# LineFollower.net
KiCad netlist of a schematic drawn in Altium Designer
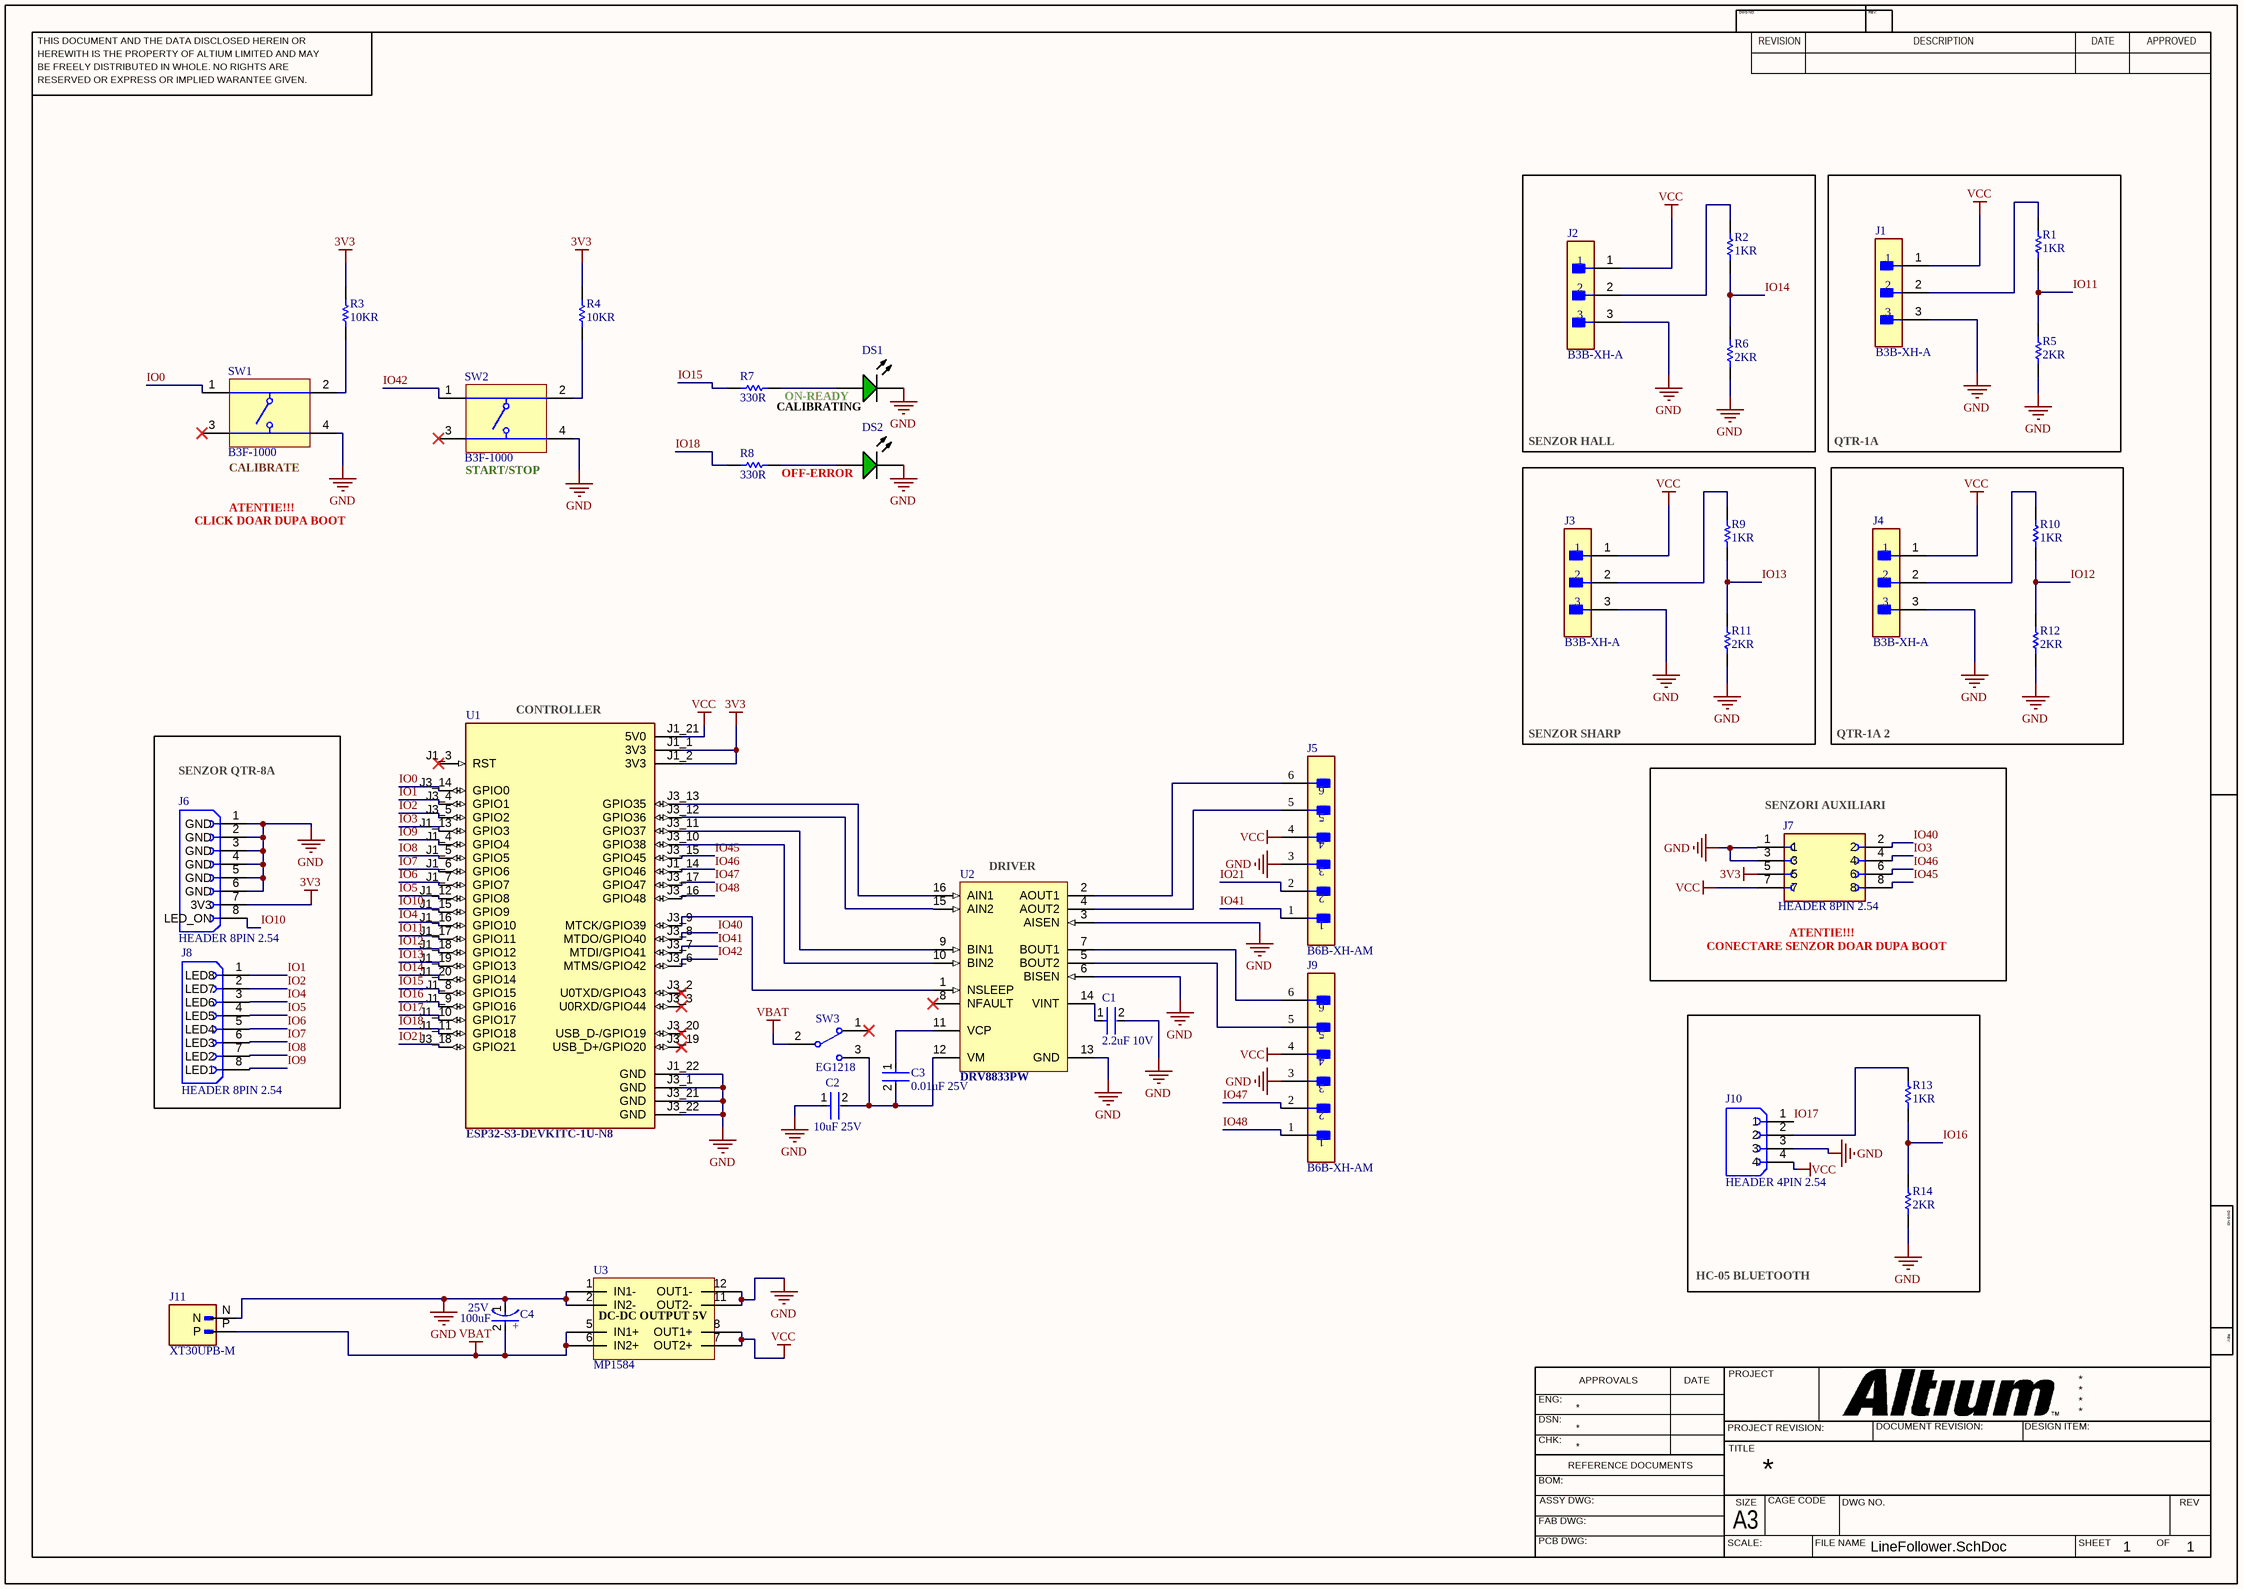
[diagram p0: LineFollower.SchDoc]

(export (version "E")
  (design (tool "Eeschema 10.0.6"))
  (components
    (comp (ref "C1")
      (value "2.2uF 10V")
      (footprint "FP-CL21-IPC_B")
      (description "CL21 Series 0805 10uF 25V ±20% Tolerance X5R Multilayer Ceramic Chip Capacitor")
      (libsource (lib "Altium Content Vault") (part "b4654b650e69147ec39a6b967a45e02"))
    )
    (comp (ref "C2")
      (value "10uF 25V")
      (footprint "FP-CL21-IPC_B")
      (description "CL21 Series 0805 10uF 25V ±20% Tolerance X5R Multilayer Ceramic Chip Capacitor")
      (libsource (lib "Altium Content Vault") (part "b4654b650e69147ec39a6b967a45e02"))
    )
    (comp (ref "C3")
      (value "0.01uF 25V")
      (footprint "FP-CL21-IPC_B")
      (description "CL21 Series 0805 10uF 25V ±20% Tolerance X5R Multilayer Ceramic Chip Capacitor")
      (libsource (lib "Altium Content Vault") (part "b4654b650e69147ec39a6b967a45e02"))
    )
    (comp (ref "C4")
      (value "EEUTA1E101")
      (footprint "FP-RAD-TH-D_8_0_5-L_11_5-MFG")
      (description "Aluminum Electrolytic Capacitors (Radial Lead Type) AEC-Q200 Qualified 100uF ±20% 25V")
      (fields
        (field (name "VOLTAGE") "25V")
        (field (name "TOLERANCE") "20%")
        (field (name "CAPACITANCE") "100uF")
      )
      (libsource (lib "Altium Content Vault") (part "203bc49f2ac43e59fd269a8c329ed05"))
    )
    (comp (ref "DS1")
      (value "304090040")
      (footprint "LED-2P-2.28-3MM")
      (description "Green LED, 80 mW, 20 mA, -25 to 85 degC, 2-Pin THD")
      (fields (field (name "MANUFACTURER") "Shenzhen CGX"))
      (libsource (lib "Costel Petrea3006") (part "LED-GREEN-AK-2"))
    )
    (comp (ref "DS2")
      (value "304090040")
      (footprint "LED-2P-2.28-3MM")
      (description "Green LED, 80 mW, 20 mA, -25 to 85 degC, 2-Pin THD")
      (fields (field (name "MANUFACTURER") "Shenzhen CGX"))
      (libsource (lib "Costel Petrea3006") (part "LED-GREEN-AK-2"))
    )
    (comp (ref "J1")
      (value "B3B-XH-A")
      (footprint "FP-B3B-XH-A_LF_SN-MFG")
      (description "CONN HEADER VERT 3POS 2.5MM")
      (libsource (lib "Altium Content Vault") (part "0d3f023dd272f625e17a2be33dea85f"))
    )
    (comp (ref "J2")
      (value "B3B-XH-A")
      (footprint "FP-B3B-XH-A_LF_SN-MFG")
      (description "CONN HEADER VERT 3POS 2.5MM")
      (libsource (lib "Altium Content Vault") (part "0d3f023dd272f625e17a2be33dea85f"))
    )
    (comp (ref "J3")
      (value "B3B-XH-A")
      (footprint "FP-B3B-XH-A_LF_SN-MFG")
      (description "CONN HEADER VERT 3POS 2.5MM")
      (libsource (lib "Altium Content Vault") (part "0d3f023dd272f625e17a2be33dea85f"))
    )
    (comp (ref "J4")
      (value "B3B-XH-A")
      (footprint "FP-B3B-XH-A_LF_SN-MFG")
      (description "CONN HEADER VERT 3POS 2.5MM")
      (libsource (lib "Altium Content Vault") (part "0d3f023dd272f625e17a2be33dea85f"))
    )
    (comp (ref "J5")
      (value "B6B-XH-AM")
      (footprint "FP-B6B-XH-AM_LF_SN-MFG")
      (description "CONN HEADER VERT 6POS 2.5MM")
      (libsource (lib "Altium Content Vault") (part "f2cb566baf1c37ab5a3b8e90bbeafd6"))
    )
    (comp (ref "J6")
      (value "HEADER 8PIN 2.54")
      (footprint "GRAVITECH_8FX1-254MM")
      (description "Headers & Wire Housings 2.54MM 0.1 8-PIN FEMALE HEADER")
      (fields (field (name "MP") "8Fx1-254mm") (field (name "MF") "Gravitech"))
      (libsource (lib "8FX1-254MM") (part "8FX1-254MM"))
    )
    (comp (ref "J7")
      (value "HEADER 8PIN 2.54")
      (footprint "SULLINS_PPPC042LFBN-RC")
      (description "8 Position Total Dual Row 2.54 mm Pitch Straight Female Header")
      (fields (field (name "MF") "Sullins Connector Solutions") (field (name "MP") "PPPC042LFBNRC"))
      (libsource (lib "PPPC042LFBN-RC") (part "PPPC042LFBN-RC"))
    )
    (comp (ref "J8")
      (value "HEADER 8PIN 2.54")
      (footprint "GRAVITECH_8FX1-254MM")
      (description "Headers & Wire Housings 2.54MM 0.1 8-PIN FEMALE HEADER")
      (fields (field (name "MP") "8Fx1-254mm") (field (name "MF") "Gravitech"))
      (libsource (lib "8FX1-254MM") (part "8FX1-254MM"))
    )
    (comp (ref "J9")
      (value "B6B-XH-AM")
      (footprint "FP-B6B-XH-AM_LF_SN-MFG")
      (description "CONN HEADER VERT 6POS 2.5MM")
      (libsource (lib "Altium Content Vault") (part "f2cb566baf1c37ab5a3b8e90bbeafd6"))
    )
    (comp (ref "J10")
      (value "HEADER 4PIN 2.54")
      (footprint "SULLINS_PPTC041LFBN-RC")
      (description "4 Position Header Connector 0.100 (2.54mm) Through Hole Tin")
      (fields (field (name "MF") "Sullins Connector") (field (name "MP") "PPTC041LFBN-RC"))
      (libsource (lib "PPTC041LFBN-RC") (part "PPTC041LFBN-RC"))
    )
    (comp (ref "J11")
      (value "XT30UPB-M")
      (footprint "AMASS_XT30UPB-M")
      (description "Socket; DC supply; XT30; male; PIN: 2; on PCBs; THT; yellow; 15A; 500V")
      (fields (field (name "MF") "amass"))
      (libsource (lib "XT30") (part "XT30UPB-M"))
    )
    (comp (ref "R1")
      (value "1KR")
      (footprint "RESC2013X60X30LL20T20")
      (fields (field (name "MANUFACTURER") "KOA Speer") (field (name "PART NUMBER") "SG73S2ATTD1002F"))
      (libsource (lib "Altium Content Vault") (part "RES"))
    )
    (comp (ref "R2")
      (value "1KR")
      (footprint "RESC2013X60X30LL20T20")
      (fields (field (name "MANUFACTURER") "KOA Speer") (field (name "PART NUMBER") "SG73S2ATTD1002F"))
      (libsource (lib "Altium Content Vault") (part "RES"))
    )
    (comp (ref "R3")
      (value "10KR")
      (footprint "RESC2013X60X30LL20T20")
      (fields (field (name "MANUFACTURER") "KOA Speer") (field (name "PART NUMBER") "SG73S2ATTD1002F"))
      (libsource (lib "Altium Content Vault") (part "RES"))
    )
    (comp (ref "R4")
      (value "10KR")
      (footprint "RESC2013X60X30LL20T20")
      (fields (field (name "MANUFACTURER") "KOA Speer") (field (name "PART NUMBER") "SG73S2ATTD1002F"))
      (libsource (lib "Altium Content Vault") (part "RES"))
    )
    (comp (ref "R5")
      (value "2KR")
      (footprint "RESC2013X60X30LL20T20")
      (fields (field (name "MANUFACTURER") "KOA Speer") (field (name "PART NUMBER") "SG73S2ATTD1002F"))
      (libsource (lib "Altium Content Vault") (part "RES"))
    )
    (comp (ref "R6")
      (value "2KR")
      (footprint "RESC2013X60X30LL20T20")
      (fields (field (name "MANUFACTURER") "KOA Speer") (field (name "PART NUMBER") "SG73S2ATTD1002F"))
      (libsource (lib "Altium Content Vault") (part "RES"))
    )
    (comp (ref "R7")
      (value "330R")
      (footprint "RESC2013X60X30LL20T20")
      (fields (field (name "MANUFACTURER") "KOA Speer") (field (name "PART NUMBER") "SG73S2ATTD1002F"))
      (libsource (lib "Altium Content Vault") (part "RES"))
    )
    (comp (ref "R8")
      (value "330R")
      (footprint "RESC2013X60X30LL20T20")
      (fields (field (name "MANUFACTURER") "KOA Speer") (field (name "PART NUMBER") "SG73S2ATTD1002F"))
      (libsource (lib "Altium Content Vault") (part "RES"))
    )
    (comp (ref "R9")
      (value "1KR")
      (footprint "RESC2013X60X30LL20T20")
      (fields (field (name "MANUFACTURER") "KOA Speer") (field (name "PART NUMBER") "SG73S2ATTD1002F"))
      (libsource (lib "Altium Content Vault") (part "RES"))
    )
    (comp (ref "R10")
      (value "1KR")
      (footprint "RESC2013X60X30LL20T20")
      (fields (field (name "MANUFACTURER") "KOA Speer") (field (name "PART NUMBER") "SG73S2ATTD1002F"))
      (libsource (lib "Altium Content Vault") (part "RES"))
    )
    (comp (ref "R11")
      (value "2KR")
      (footprint "RESC2013X60X30LL20T20")
      (fields (field (name "MANUFACTURER") "KOA Speer") (field (name "PART NUMBER") "SG73S2ATTD1002F"))
      (libsource (lib "Altium Content Vault") (part "RES"))
    )
    (comp (ref "R12")
      (value "2KR")
      (footprint "RESC2013X60X30LL20T20")
      (fields (field (name "MANUFACTURER") "KOA Speer") (field (name "PART NUMBER") "SG73S2ATTD1002F"))
      (libsource (lib "Altium Content Vault") (part "RES"))
    )
    (comp (ref "R13")
      (value "1KR")
      (footprint "RESC2013X60X30LL20T20")
      (fields (field (name "MANUFACTURER") "KOA Speer") (field (name "PART NUMBER") "SG73S2ATTD1002F"))
      (libsource (lib "Altium Content Vault") (part "RES"))
    )
    (comp (ref "R14")
      (value "2KR")
      (footprint "RESC2013X60X30LL20T20")
      (fields (field (name "MANUFACTURER") "KOA Speer") (field (name "PART NUMBER") "SG73S2ATTD1002F"))
      (libsource (lib "Altium Content Vault") (part "RES"))
    )
    (comp (ref "SW1")
      (value "B3F-1000")
      (footprint "OMRON-B3F-1000-4_V")
      (description "Tactile Switch, SPST-NO, 0.05 A, 24 V, -25 to 70 degC, 4-Pin THD, RoHS, Bulk")
      (fields (field (name "MANUFACTURER") "Omron Electronic Components"))
      (libsource (lib "Costel Petrea3006") (part "SW-SPST-4_A"))
    )
    (comp (ref "SW2")
      (value "B3F-1000")
      (footprint "OMRON-B3F-1000-4_V")
      (description "Tactile Switch, SPST-NO, 0.05 A, 24 V, -25 to 70 degC, 4-Pin THD, RoHS, Bulk")
      (fields (field (name "MANUFACTURER") "Omron Electronic Components"))
      (libsource (lib "Costel Petrea3006") (part "SW-SPST-4_A"))
    )
    (comp (ref "SW3")
      (value "EG1218")
      (footprint "ESWI-EG1218_V")
      (description "Slide Switch, 500 V, -20 to 70 degC, 3-Pin THD, RoHS")
      (libsource (lib "Altium Content Vault") (part "SW-SPDT-3_B"))
    )
    (comp (ref "U1")
      (value "ESP32-S3-DEVKITC-1U-N8")
      (footprint "MODULE_ESP32-S3-DEVKITC-1U-N8R8")
      (fields (field (name "MF") "Espressif Systems") (field (name "MP") "ESP32-S3-DEVKITC-1U-N8R8"))
      (libsource (lib "ESP32-S3-DEVKITC-1U-N8R8") (part "ESP32-S3-DEVKITC-1U-N8R8"))
    )
    (comp (ref "U2")
      (value "DRV8833PW")
      (footprint "PW0016A_M")
      (fields (field (name "MANUFACTURER") "Texas Instruments"))
      (libsource (lib "Altium Content Vault") (part "TI-DRV8833PW-16"))
    )
    (comp (ref "U3") (value "MP1584") (footprint "MP1584") (libsource (lib "mp1584") (part "MP1584")))
  )
  (nets
    (net (code "2") (name "/IO0") (class "Default")
      (node (ref "SW1") (pin "1") (pinfunction "1_1") (pintype "passive"))
      (node (ref "U1") (pin "J3_14") (pinfunction "GPIO0_J3_14") (pintype "bidirectional"))
    )
    (net (code "3") (name "/IO1") (class "Default")
      (node (ref "J8") (pin "1") (pinfunction "GND_1") (pintype "passive"))
      (node (ref "U1") (pin "J3_4") (pinfunction "GPIO1_J3_4") (pintype "bidirectional"))
    )
    (net (code "4") (name "/IO2") (class "Default")
      (node (ref "J8") (pin "2") (pinfunction "GND_2") (pintype "passive"))
      (node (ref "U1") (pin "J3_5") (pinfunction "GPIO2_J3_5") (pintype "bidirectional"))
    )
    (net (code "5") (name "/IO3") (class "Default")
      (node (ref "J7") (pin "4") (pinfunction "4_4") (pintype "passive"))
      (node (ref "U1") (pin "J1_13") (pinfunction "GPIO3_J1_13") (pintype "bidirectional"))
    )
    (net (code "6") (name "/IO4") (class "Default")
      (node (ref "J8") (pin "3") (pinfunction "GND_3") (pintype "passive"))
      (node (ref "U1") (pin "J1_16") (pinfunction "GPIO10_J1_16") (pintype "bidirectional"))
    )
    (net (code "7") (name "/IO5") (class "Default")
      (node (ref "J8") (pin "4") (pinfunction "GND_4") (pintype "passive"))
      (node (ref "U1") (pin "J1_12") (pinfunction "GPIO8_J1_12") (pintype "bidirectional"))
    )
    (net (code "8") (name "/IO6") (class "Default")
      (node (ref "J8") (pin "5") (pinfunction "GND_5") (pintype "passive"))
      (node (ref "U1") (pin "J1_7") (pinfunction "GPIO7_J1_7") (pintype "bidirectional"))
    )
    (net (code "9") (name "/IO7") (class "Default")
      (node (ref "J8") (pin "6") (pinfunction "GND_6") (pintype "passive"))
      (node (ref "U1") (pin "J1_6") (pinfunction "GPIO6_J1_6") (pintype "bidirectional"))
    )
    (net (code "10") (name "/IO8") (class "Default")
      (node (ref "J8") (pin "7") (pinfunction "3V3_7") (pintype "passive"))
      (node (ref "U1") (pin "J1_5") (pinfunction "GPIO5_J1_5") (pintype "bidirectional"))
    )
    (net (code "11") (name "/IO9") (class "Default")
      (node (ref "J8") (pin "8") (pinfunction "LED_ON_8") (pintype "passive"))
      (node (ref "U1") (pin "J1_4") (pinfunction "GPIO4_J1_4") (pintype "bidirectional"))
    )
    (net (code "12") (name "/IO10") (class "Default")
      (node (ref "J6") (pin "8") (pinfunction "LED_ON_8") (pintype "passive"))
      (node (ref "U1") (pin "J1_15") (pinfunction "GPIO9_J1_15") (pintype "bidirectional"))
    )
    (net (code "13") (name "/IO11") (class "Default")
      (node (ref "R1") (pin "1") (pinfunction "1_1") (pintype "passive"))
      (node (ref "R5") (pin "2") (pinfunction "2_2") (pintype "passive"))
      (node (ref "U1") (pin "J1_17") (pinfunction "GPIO11_J1_17") (pintype "bidirectional"))
    )
    (net (code "14") (name "/IO12") (class "Default")
      (node (ref "R10") (pin "1") (pinfunction "1_1") (pintype "passive"))
      (node (ref "R12") (pin "2") (pinfunction "2_2") (pintype "passive"))
      (node (ref "U1") (pin "J1_18") (pinfunction "GPIO12_J1_18") (pintype "bidirectional"))
    )
    (net (code "15") (name "/IO13") (class "Default")
      (node (ref "R11") (pin "2") (pinfunction "2_2") (pintype "passive"))
      (node (ref "R9") (pin "1") (pinfunction "1_1") (pintype "passive"))
      (node (ref "U1") (pin "J1_19") (pinfunction "GPIO13_J1_19") (pintype "bidirectional"))
    )
    (net (code "16") (name "/IO14") (class "Default")
      (node (ref "R2") (pin "1") (pinfunction "1_1") (pintype "passive"))
      (node (ref "R6") (pin "2") (pinfunction "2_2") (pintype "passive"))
      (node (ref "U1") (pin "J1_20") (pinfunction "GPIO14_J1_20") (pintype "bidirectional"))
    )
    (net (code "17") (name "/IO15") (class "Default")
      (node (ref "R7") (pin "2") (pinfunction "2_2") (pintype "passive"))
      (node (ref "U1") (pin "J1_8") (pinfunction "GPIO15_J1_8") (pintype "bidirectional"))
    )
    (net (code "18") (name "/IO16") (class "Default")
      (node (ref "R13") (pin "1") (pinfunction "1_1") (pintype "passive"))
      (node (ref "R14") (pin "2") (pinfunction "2_2") (pintype "passive"))
      (node (ref "U1") (pin "J1_9") (pinfunction "GPIO16_J1_9") (pintype "bidirectional"))
    )
    (net (code "19") (name "/IO17") (class "Default")
      (node (ref "J10") (pin "1") (pinfunction "1_1") (pintype "passive"))
      (node (ref "U1") (pin "J1_10") (pinfunction "GPIO17_J1_10") (pintype "bidirectional"))
    )
    (net (code "20") (name "/IO18") (class "Default")
      (node (ref "R8") (pin "2") (pinfunction "2_2") (pintype "passive"))
      (node (ref "U1") (pin "J1_11") (pinfunction "GPIO18_J1_11") (pintype "bidirectional"))
    )
    (net (code "21") (name "/IO21") (class "Default")
      (node (ref "J5") (pin "2") (pinfunction "2_2") (pintype "passive"))
      (node (ref "U1") (pin "J3_18") (pinfunction "GPIO21_J3_18") (pintype "bidirectional"))
    )
    (net (code "22") (name "/IO40") (class "Default")
      (node (ref "J7") (pin "2") (pinfunction "2_2") (pintype "passive"))
      (node (ref "U1") (pin "J3_8") (pinfunction "MTDO/GPIO40_J3_8") (pintype "bidirectional"))
    )
    (net (code "23") (name "/IO41") (class "Default")
      (node (ref "J5") (pin "1") (pinfunction "1_1") (pintype "passive"))
      (node (ref "U1") (pin "J3_7") (pinfunction "MTDI/GPIO41_J3_7") (pintype "bidirectional"))
    )
    (net (code "24") (name "/IO42") (class "Default")
      (node (ref "SW2") (pin "1") (pinfunction "1_1") (pintype "passive"))
      (node (ref "U1") (pin "J3_6") (pinfunction "MTMS/GPIO42_J3_6") (pintype "bidirectional"))
    )
    (net (code "25") (name "/IO45") (class "Default")
      (node (ref "J7") (pin "8") (pinfunction "8_8") (pintype "passive"))
      (node (ref "U1") (pin "J3_15") (pinfunction "GPIO45_J3_15") (pintype "bidirectional"))
    )
    (net (code "26") (name "/IO46") (class "Default")
      (node (ref "J7") (pin "6") (pinfunction "6_6") (pintype "passive"))
      (node (ref "U1") (pin "J1_14") (pinfunction "GPIO46_J1_14") (pintype "bidirectional"))
    )
    (net (code "27") (name "/IO47") (class "Default")
      (node (ref "J9") (pin "2") (pinfunction "2_2") (pintype "passive"))
      (node (ref "U1") (pin "J3_17") (pinfunction "GPIO47_J3_17") (pintype "bidirectional"))
    )
    (net (code "28") (name "/IO48") (class "Default")
      (node (ref "J9") (pin "1") (pinfunction "1_1") (pintype "passive"))
      (node (ref "U1") (pin "J3_16") (pinfunction "GPIO48_J3_16") (pintype "bidirectional"))
    )
    (net (code "29") (name "3V3") (class "Default")
      (node (ref "J6") (pin "7") (pinfunction "3V3_7") (pintype "passive"))
      (node (ref "J7") (pin "5") (pinfunction "5_5") (pintype "passive"))
      (node (ref "R3") (pin "2") (pinfunction "2_2") (pintype "passive"))
      (node (ref "R4") (pin "2") (pinfunction "2_2") (pintype "passive"))
      (node (ref "U1") (pin "J1_1") (pinfunction "3V3_J1_1") (pintype "power_in"))
      (node (ref "U1") (pin "J1_2") (pinfunction "3V3_J1_2") (pintype "power_in"))
    )
    (net (code "30") (name "GND") (class "Default")
      (node (ref "C1") (pin "2") (pinfunction "2_2") (pintype "passive"))
      (node (ref "C2") (pin "1") (pinfunction "1_1") (pintype "passive"))
      (node (ref "C4") (pin "1") (pinfunction "C_1") (pintype "passive"))
      (node (ref "DS1") (pin "2") (pinfunction "K_2") (pintype "passive"))
      (node (ref "DS2") (pin "2") (pinfunction "K_2") (pintype "passive"))
      (node (ref "J1") (pin "3") (pinfunction "3_3") (pintype "passive"))
      (node (ref "J10") (pin "3") (pinfunction "3_3") (pintype "passive"))
      (node (ref "J11") (pin "N") (pinfunction "N_N") (pintype "passive"))
      (node (ref "J2") (pin "3") (pinfunction "3_3") (pintype "passive"))
      (node (ref "J3") (pin "3") (pinfunction "3_3") (pintype "passive"))
      (node (ref "J4") (pin "3") (pinfunction "3_3") (pintype "passive"))
      (node (ref "J5") (pin "3") (pinfunction "3_3") (pintype "passive"))
      (node (ref "J6") (pin "1") (pinfunction "GND_1") (pintype "passive"))
      (node (ref "J6") (pin "2") (pinfunction "GND_2") (pintype "passive"))
      (node (ref "J6") (pin "3") (pinfunction "GND_3") (pintype "passive"))
      (node (ref "J6") (pin "4") (pinfunction "GND_4") (pintype "passive"))
      (node (ref "J6") (pin "5") (pinfunction "GND_5") (pintype "passive"))
      (node (ref "J6") (pin "6") (pinfunction "GND_6") (pintype "passive"))
      (node (ref "J7") (pin "1") (pinfunction "1_1") (pintype "passive"))
      (node (ref "J7") (pin "3") (pinfunction "3_3") (pintype "passive"))
      (node (ref "J9") (pin "3") (pinfunction "3_3") (pintype "passive"))
      (node (ref "R11") (pin "1") (pinfunction "1_1") (pintype "passive"))
      (node (ref "R12") (pin "1") (pinfunction "1_1") (pintype "passive"))
      (node (ref "R14") (pin "1") (pinfunction "1_1") (pintype "passive"))
      (node (ref "R5") (pin "1") (pinfunction "1_1") (pintype "passive"))
      (node (ref "R6") (pin "1") (pinfunction "1_1") (pintype "passive"))
      (node (ref "SW1") (pin "4") (pinfunction "4_4") (pintype "passive"))
      (node (ref "SW2") (pin "4") (pinfunction "4_4") (pintype "passive"))
      (node (ref "U1") (pin "J1_22") (pinfunction "GND_J1_22") (pintype "power_in"))
      (node (ref "U1") (pin "J3_1") (pinfunction "GND_J3_1") (pintype "power_in"))
      (node (ref "U1") (pin "J3_21") (pinfunction "GND_J3_21") (pintype "power_in"))
      (node (ref "U1") (pin "J3_22") (pinfunction "GND_J3_22") (pintype "power_in"))
      (node (ref "U2") (pin "13") (pinfunction "GND_13") (pintype "power_in"))
      (node (ref "U2") (pin "3") (pinfunction "AISEN_3") (pintype "input"))
      (node (ref "U2") (pin "6") (pinfunction "BISEN_6") (pintype "input"))
      (node (ref "U3") (pin "1") (pinfunction "IN1-_1") (pintype "passive"))
      (node (ref "U3") (pin "11") (pinfunction "OUT2-_11") (pintype "passive"))
      (node (ref "U3") (pin "12") (pinfunction "OUT1-_12") (pintype "passive"))
      (node (ref "U3") (pin "2") (pinfunction "IN2-_2") (pintype "passive"))
    )
    (net (code "31") (name "Net-(DS1-A)") (class "Default")
      (node (ref "DS1") (pin "1") (pinfunction "A_1") (pintype "passive"))
      (node (ref "R7") (pin "1") (pinfunction "1_1") (pintype "passive"))
    )
    (net (code "32") (name "Net-(DS2-A)") (class "Default")
      (node (ref "DS2") (pin "1") (pinfunction "A_1") (pintype "passive"))
      (node (ref "R8") (pin "1") (pinfunction "1_1") (pintype "passive"))
    )
    (net (code "33") (name "Net-(J1-Pad2)") (class "Default")
      (node (ref "J1") (pin "2") (pinfunction "2_2") (pintype "passive"))
      (node (ref "R1") (pin "2") (pinfunction "2_2") (pintype "passive"))
    )
    (net (code "34") (name "Net-(J2-Pad2)") (class "Default")
      (node (ref "J2") (pin "2") (pinfunction "2_2") (pintype "passive"))
      (node (ref "R2") (pin "2") (pinfunction "2_2") (pintype "passive"))
    )
    (net (code "35") (name "Net-(J3-Pad2)") (class "Default")
      (node (ref "J3") (pin "2") (pinfunction "2_2") (pintype "passive"))
      (node (ref "R9") (pin "2") (pinfunction "2_2") (pintype "passive"))
    )
    (net (code "36") (name "Net-(J4-Pad2)") (class "Default")
      (node (ref "J4") (pin "2") (pinfunction "2_2") (pintype "passive"))
      (node (ref "R10") (pin "2") (pinfunction "2_2") (pintype "passive"))
    )
    (net (code "37") (name "Net-(J10-Pad2)") (class "Default")
      (node (ref "J10") (pin "2") (pinfunction "2_2") (pintype "passive"))
      (node (ref "R13") (pin "2") (pinfunction "2_2") (pintype "passive"))
    )
    (net (code "38") (name "Net-(R3-Pad1)") (class "Default")
      (node (ref "R3") (pin "1") (pinfunction "1_1") (pintype "passive"))
      (node (ref "SW1") (pin "2") (pinfunction "2_2") (pintype "passive"))
    )
    (net (code "39") (name "Net-(R4-Pad1)") (class "Default")
      (node (ref "R4") (pin "1") (pinfunction "1_1") (pintype "passive"))
      (node (ref "SW2") (pin "2") (pinfunction "2_2") (pintype "passive"))
    )
    (net (code "40") (name "Net-(U1-GPIO35)") (class "Default")
      (node (ref "U1") (pin "J3_13") (pinfunction "GPIO35_J3_13") (pintype "bidirectional"))
      (node (ref "U2") (pin "16") (pinfunction "AIN1_16") (pintype "input"))
    )
    (net (code "41") (name "Net-(U1-GPIO36)") (class "Default")
      (node (ref "U1") (pin "J3_12") (pinfunction "GPIO36_J3_12") (pintype "bidirectional"))
      (node (ref "U2") (pin "15") (pinfunction "AIN2_15") (pintype "input"))
    )
    (net (code "42") (name "Net-(U1-GPIO37)") (class "Default")
      (node (ref "U1") (pin "J3_11") (pinfunction "GPIO37_J3_11") (pintype "bidirectional"))
      (node (ref "U2") (pin "9") (pinfunction "BIN1_9") (pintype "input"))
    )
    (net (code "43") (name "Net-(U1-GPIO38)") (class "Default")
      (node (ref "U1") (pin "J3_10") (pinfunction "GPIO38_J3_10") (pintype "bidirectional"))
      (node (ref "U2") (pin "10") (pinfunction "BIN2_10") (pintype "input"))
    )
    (net (code "44") (name "Net-(U1-MTCK{slash}GPIO39)") (class "Default")
      (node (ref "U1") (pin "J3_9") (pinfunction "MTCK/GPIO39_J3_9") (pintype "bidirectional"))
      (node (ref "U2") (pin "1") (pinfunction "NSLEEP_1") (pintype "input"))
    )
    (net (code "45") (name "Net-(U2-AOUT1)") (class "Default")
      (node (ref "J5") (pin "6") (pinfunction "6_6") (pintype "passive"))
      (node (ref "U2") (pin "2") (pinfunction "AOUT1_2") (pintype "tri_state"))
    )
    (net (code "46") (name "Net-(U2-AOUT2)") (class "Default")
      (node (ref "J5") (pin "5") (pinfunction "5_5") (pintype "passive"))
      (node (ref "U2") (pin "4") (pinfunction "AOUT2_4") (pintype "tri_state"))
    )
    (net (code "47") (name "Net-(U2-BOUT1)") (class "Default")
      (node (ref "J9") (pin "6") (pinfunction "6_6") (pintype "passive"))
      (node (ref "U2") (pin "7") (pinfunction "BOUT1_7") (pintype "tri_state"))
    )
    (net (code "48") (name "Net-(U2-BOUT2)") (class "Default")
      (node (ref "J9") (pin "5") (pinfunction "5_5") (pintype "passive"))
      (node (ref "U2") (pin "5") (pinfunction "BOUT2_5") (pintype "tri_state"))
    )
    (net (code "49") (name "Net-(U2-VCP)") (class "Default")
      (node (ref "C3") (pin "1") (pinfunction "1_1") (pintype "passive"))
      (node (ref "U2") (pin "11") (pinfunction "VCP_11") (pintype "passive"))
    )
    (net (code "50") (name "Net-(U2-VINT)") (class "Default")
      (node (ref "C1") (pin "1") (pinfunction "1_1") (pintype "passive"))
      (node (ref "U2") (pin "14") (pinfunction "VINT_14") (pintype "passive"))
    )
    (net (code "51") (name "Net-(U2-VM)") (class "Default")
      (node (ref "C2") (pin "2") (pinfunction "2_2") (pintype "passive"))
      (node (ref "C3") (pin "2") (pinfunction "2_2") (pintype "passive"))
      (node (ref "SW3") (pin "3") (pinfunction "3_3") (pintype "passive"))
      (node (ref "U2") (pin "12") (pinfunction "VM_12") (pintype "power_in"))
    )
    (net (code "52") (name "VBAT") (class "Default")
      (node (ref "C4") (pin "2") (pinfunction "A_2") (pintype "passive"))
      (node (ref "J11") (pin "P") (pinfunction "P_P") (pintype "passive"))
      (node (ref "SW3") (pin "2") (pinfunction "COM_2") (pintype "passive"))
      (node (ref "U3") (pin "5") (pinfunction "IN1+_5") (pintype "passive"))
      (node (ref "U3") (pin "6") (pinfunction "IN2+_6") (pintype "passive"))
    )
    (net (code "53") (name "VCC") (class "Default")
      (node (ref "J1") (pin "1") (pinfunction "1_1") (pintype "passive"))
      (node (ref "J10") (pin "4") (pinfunction "4_4") (pintype "passive"))
      (node (ref "J2") (pin "1") (pinfunction "1_1") (pintype "passive"))
      (node (ref "J3") (pin "1") (pinfunction "1_1") (pintype "passive"))
      (node (ref "J4") (pin "1") (pinfunction "1_1") (pintype "passive"))
      (node (ref "J5") (pin "4") (pinfunction "4_4") (pintype "passive"))
      (node (ref "J7") (pin "7") (pinfunction "7_7") (pintype "passive"))
      (node (ref "J9") (pin "4") (pinfunction "4_4") (pintype "passive"))
      (node (ref "U1") (pin "J1_21") (pinfunction "5V0_J1_21") (pintype "power_in"))
      (node (ref "U3") (pin "7") (pinfunction "OUT2+_7") (pintype "passive"))
      (node (ref "U3") (pin "8") (pinfunction "OUT1+_8") (pintype "passive"))
    )
    (net (code "54") (name "unconnected-(SW1-Pad3)") (class "Default")
      (node (ref "SW1") (pin "3") (pinfunction "3_3") (pintype "passive+no_connect"))
    )
    (net (code "55") (name "unconnected-(SW2-Pad3)") (class "Default")
      (node (ref "SW2") (pin "3") (pinfunction "3_3") (pintype "passive+no_connect"))
    )
    (net (code "56") (name "unconnected-(SW3-Pad1)") (class "Default")
      (node (ref "SW3") (pin "1") (pinfunction "1_1") (pintype "passive+no_connect"))
    )
    (net (code "57") (name "unconnected-(U1-RST-PadJ1_3)") (class "Default")
      (node (ref "U1") (pin "J1_3") (pinfunction "RST_J1_3") (pintype "input+no_connect"))
    )
    (net (code "58") (name "unconnected-(U1-U0RXD{slash}GPIO44-PadJ3_3)") (class "Default")
      (node (ref "U1") (pin "J3_3") (pinfunction "U0RXD/GPIO44_J3_3") (pintype "bidirectional+no_connect"))
    )
    (net (code "59") (name "unconnected-(U1-U0TXD{slash}GPIO43-PadJ3_2)") (class "Default")
      (node (ref "U1") (pin "J3_2") (pinfunction "U0TXD/GPIO43_J3_2") (pintype "bidirectional+no_connect"))
    )
    (net (code "60") (name "unconnected-(U1-USB_D+{slash}GPIO20-PadJ3_19)") (class "Default")
      (node (ref "U1") (pin "J3_19") (pinfunction "USB_D+/GPIO20_J3_19") (pintype "bidirectional+no_connect"))
    )
    (net (code "61") (name "unconnected-(U1-USB_D-{slash}GPIO19-PadJ3_20)") (class "Default")
      (node (ref "U1") (pin "J3_20") (pinfunction "USB_D-/GPIO19_J3_20") (pintype "bidirectional+no_connect"))
    )
    (net (code "62") (name "unconnected-(U2-NFAULT-Pad8)") (class "Default")
      (node (ref "U2") (pin "8") (pinfunction "NFAULT_8") (pintype "open_collector+no_connect"))
    )
  )
)
